# sensors.net
KiCad netlist of a schematic drawn in EAGLE
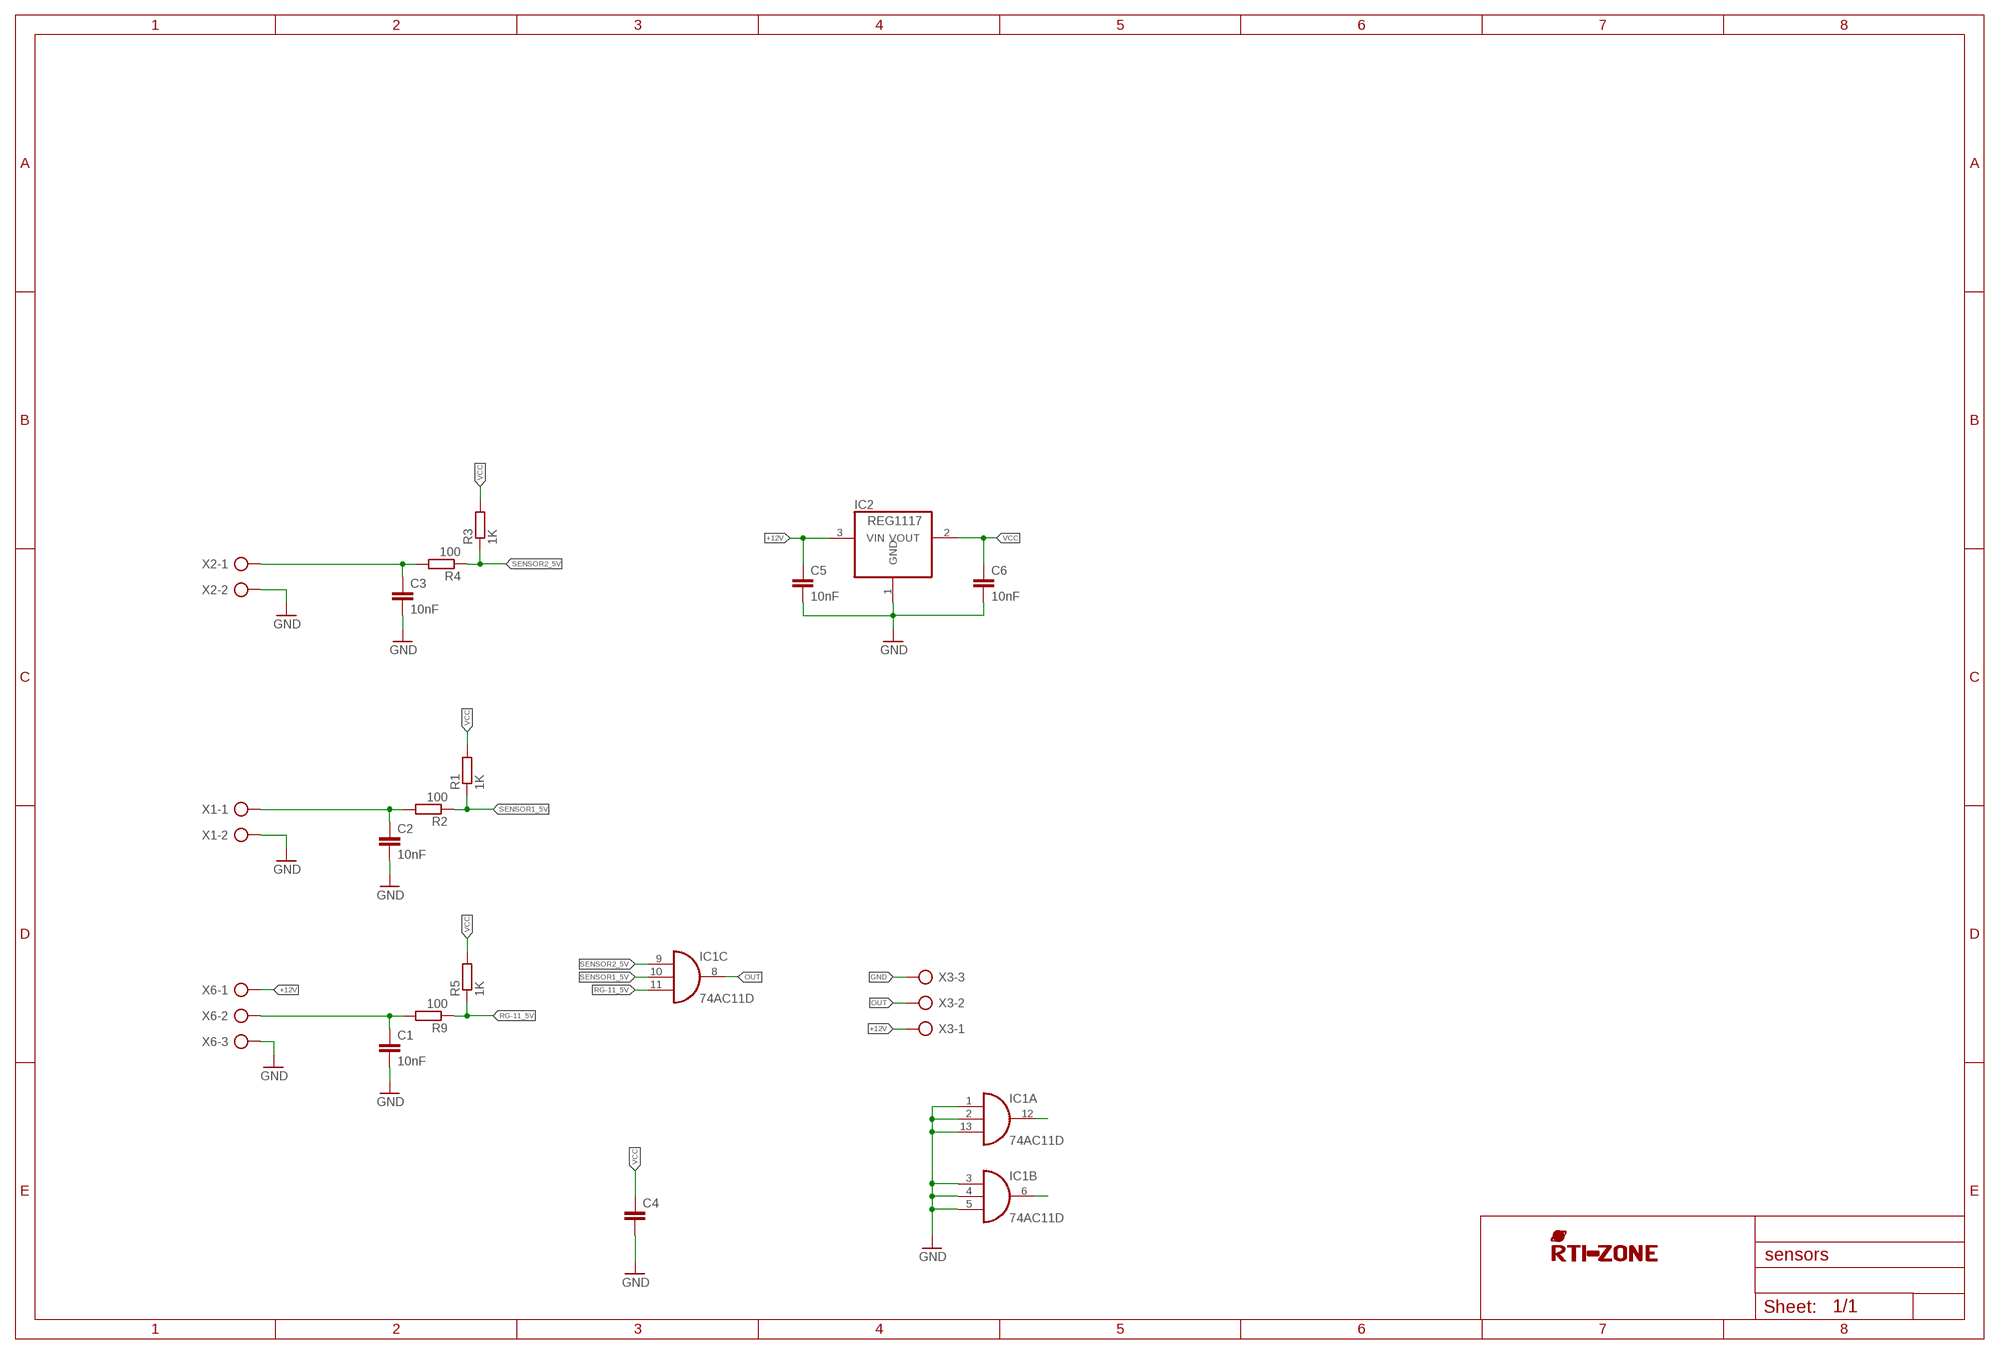
[diagram p0: schematic, sheet 1]

(export (version "E")
  (design (tool "Eeschema 10.0.6"))
  (components
    (comp (ref "C1")
      (value "10nF")
      (footprint "eagle-import:C0805")
      (libsource (lib "eagle-import") (part "C-EU'0805'"))
    )
    (comp (ref "C2")
      (value "10nF")
      (footprint "eagle-import:C0805")
      (libsource (lib "eagle-import") (part "C-EU'0805'"))
    )
    (comp (ref "C3")
      (value "10nF")
      (footprint "eagle-import:C0805")
      (libsource (lib "eagle-import") (part "C-EU'0805'"))
    )
    (comp (ref "C4")
      (value "C-EU'1206'")
      (footprint "eagle-import:C1206")
      (libsource (lib "eagle-import") (part "C-EU'1206'"))
    )
    (comp (ref "C5")
      (value "10nF")
      (footprint "eagle-import:C0805")
      (libsource (lib "eagle-import") (part "C-EU'0805'"))
    )
    (comp (ref "C6")
      (value "10nF")
      (footprint "eagle-import:C0805")
      (libsource (lib "eagle-import") (part "C-EU'0805'"))
    )
    (comp (ref "IC1")
      (value "74AC11D")
      (footprint "eagle-import:SO14")
      (libsource (lib "eagle-import") (part "7411DAC"))
    )
    (comp (ref "IC2")
      (value "REG1117")
      (footprint "eagle-import:SOT223")
      (libsource (lib "eagle-import") (part "REG1117"))
    )
    (comp (ref "R1")
      (value "1K")
      (footprint "eagle-import:R0805")
      (libsource (lib "eagle-import") (part "R-EU'0805'"))
    )
    (comp (ref "R2")
      (value "100")
      (footprint "eagle-import:R0805")
      (libsource (lib "eagle-import") (part "R-EU'0805'"))
    )
    (comp (ref "R3")
      (value "1K")
      (footprint "eagle-import:R0805")
      (libsource (lib "eagle-import") (part "R-EU'0805'"))
    )
    (comp (ref "R4")
      (value "100")
      (footprint "eagle-import:R0805")
      (libsource (lib "eagle-import") (part "R-EU'0805'"))
    )
    (comp (ref "R5")
      (value "1K")
      (footprint "eagle-import:R0805")
      (libsource (lib "eagle-import") (part "R-EU'0805'"))
    )
    (comp (ref "R9")
      (value "100")
      (footprint "eagle-import:R0805")
      (libsource (lib "eagle-import") (part "R-EU'0805'"))
    )
    (comp (ref "U$1")
      (value "RTI-LOGO_BIG")
      (footprint "eagle-import:LOGO_BIG")
      (libsource (lib "eagle-import") (part "RTI-LOGO_BIG"))
    )
    (comp (ref "X1")
      (value "AK500/2")
      (footprint "eagle-import:AK500_2")
      (fields (field (name "MF") "Altech") (field (name "MPN") "Altech 30.702"))
      (libsource (lib "eagle-import") (part "AK500/2"))
    )
    (comp (ref "X2")
      (value "AK500/2")
      (footprint "eagle-import:AK500_2")
      (fields (field (name "MF") "Altech") (field (name "MPN") "Altech 30.702"))
      (libsource (lib "eagle-import") (part "AK500/2"))
    )
    (comp (ref "X3")
      (value "AK500/3")
      (footprint "eagle-import:AK500_3")
      (fields (field (name "MF") "Altech") (field (name "MPN") "Altech 30.703"))
      (libsource (lib "eagle-import") (part "AK500/3"))
    )
    (comp (ref "X6")
      (value "AK500/3")
      (footprint "eagle-import:AK500_3")
      (fields (field (name "MF") "Altech") (field (name "MPN") "Altech 30.703"))
      (libsource (lib "eagle-import") (part "AK500/3"))
    )
  )
  (nets
    (net (code "1") (name "+12V") (class "Default")
      (node (ref "C5") (pin "1") (pinfunction "1_1") (pintype "passive"))
      (node (ref "IC2") (pin "3") (pinfunction "VIN_3") (pintype "input"))
      (node (ref "X3") (pin "1") (pinfunction "KL_1") (pintype "passive"))
      (node (ref "X6") (pin "1") (pinfunction "KL_1") (pintype "passive"))
    )
    (net (code "2") (name "GND") (class "Default")
      (node (ref "C1") (pin "2") (pinfunction "2_2") (pintype "passive"))
      (node (ref "C2") (pin "2") (pinfunction "2_2") (pintype "passive"))
      (node (ref "C3") (pin "2") (pinfunction "2_2") (pintype "passive"))
      (node (ref "C4") (pin "2") (pinfunction "2_2") (pintype "passive"))
      (node (ref "C5") (pin "2") (pinfunction "2_2") (pintype "passive"))
      (node (ref "C6") (pin "2") (pinfunction "2_2") (pintype "passive"))
      (node (ref "IC1") (pin "1") (pinfunction "I0_1") (pintype "input"))
      (node (ref "IC1") (pin "13") (pinfunction "I2_13") (pintype "input"))
      (node (ref "IC1") (pin "2") (pinfunction "I1_2") (pintype "input"))
      (node (ref "IC1") (pin "3") (pinfunction "I0_3") (pintype "input"))
      (node (ref "IC1") (pin "4") (pinfunction "I1_4") (pintype "input"))
      (node (ref "IC1") (pin "5") (pinfunction "I2_5") (pintype "input"))
      (node (ref "IC2") (pin "1") (pinfunction "GND_1") (pintype "power_in"))
      (node (ref "X1") (pin "2") (pinfunction "KL_2") (pintype "passive"))
      (node (ref "X2") (pin "2") (pinfunction "KL_2") (pintype "passive"))
      (node (ref "X3") (pin "3") (pinfunction "KL_3") (pintype "passive"))
      (node (ref "X6") (pin "3") (pinfunction "KL_3") (pintype "passive"))
    )
    (net (code "3") (name "Net-(X1A-KL)") (class "Default")
      (node (ref "C2") (pin "1") (pinfunction "1_1") (pintype "passive"))
      (node (ref "R2") (pin "2") (pinfunction "2_2") (pintype "passive"))
      (node (ref "X1") (pin "1") (pinfunction "KL_1") (pintype "passive"))
    )
    (net (code "4") (name "Net-(X2A-KL)") (class "Default")
      (node (ref "C3") (pin "1") (pinfunction "1_1") (pintype "passive"))
      (node (ref "R4") (pin "2") (pinfunction "2_2") (pintype "passive"))
      (node (ref "X2") (pin "1") (pinfunction "KL_1") (pintype "passive"))
    )
    (net (code "5") (name "Net-(X6B-KL)") (class "Default")
      (node (ref "C1") (pin "1") (pinfunction "1_1") (pintype "passive"))
      (node (ref "R9") (pin "2") (pinfunction "2_2") (pintype "passive"))
      (node (ref "X6") (pin "2") (pinfunction "KL_2") (pintype "passive"))
    )
    (net (code "6") (name "OUT") (class "Default")
      (node (ref "IC1") (pin "8") (pinfunction "O_8") (pintype "output"))
      (node (ref "X3") (pin "2") (pinfunction "KL_2") (pintype "passive"))
    )
    (net (code "7") (name "RG-11_5V") (class "Default")
      (node (ref "IC1") (pin "11") (pinfunction "I2_11") (pintype "input"))
      (node (ref "R5") (pin "1") (pinfunction "1_1") (pintype "passive"))
      (node (ref "R9") (pin "1") (pinfunction "1_1") (pintype "passive"))
    )
    (net (code "8") (name "SENSOR1_5V") (class "Default")
      (node (ref "IC1") (pin "10") (pinfunction "I1_10") (pintype "input"))
      (node (ref "R1") (pin "1") (pinfunction "1_1") (pintype "passive"))
      (node (ref "R2") (pin "1") (pinfunction "1_1") (pintype "passive"))
    )
    (net (code "9") (name "SENSOR2_5V") (class "Default")
      (node (ref "IC1") (pin "9") (pinfunction "I0_9") (pintype "input"))
      (node (ref "R3") (pin "1") (pinfunction "1_1") (pintype "passive"))
      (node (ref "R4") (pin "1") (pinfunction "1_1") (pintype "passive"))
    )
    (net (code "10") (name "VCC") (class "Default")
      (node (ref "C4") (pin "1") (pinfunction "1_1") (pintype "passive"))
      (node (ref "C6") (pin "1") (pinfunction "1_1") (pintype "passive"))
      (node (ref "IC2") (pin "2") (pinfunction "VOUT_2") (pintype "output"))
      (node (ref "R1") (pin "2") (pinfunction "2_2") (pintype "passive"))
      (node (ref "R3") (pin "2") (pinfunction "2_2") (pintype "passive"))
      (node (ref "R5") (pin "2") (pinfunction "2_2") (pintype "passive"))
    )
    (net (code "11") (name "unconnected-(IC1A-O-Pad12)") (class "Default")
      (node (ref "IC1") (pin "12") (pinfunction "O_12") (pintype "output"))
    )
    (net (code "12") (name "unconnected-(IC1B-O-Pad6)") (class "Default")
      (node (ref "IC1") (pin "6") (pinfunction "O_6") (pintype "output"))
    )
  )
)
